# TC377TP_1.net
KiCad netlist of a schematic drawn in Altium Designer
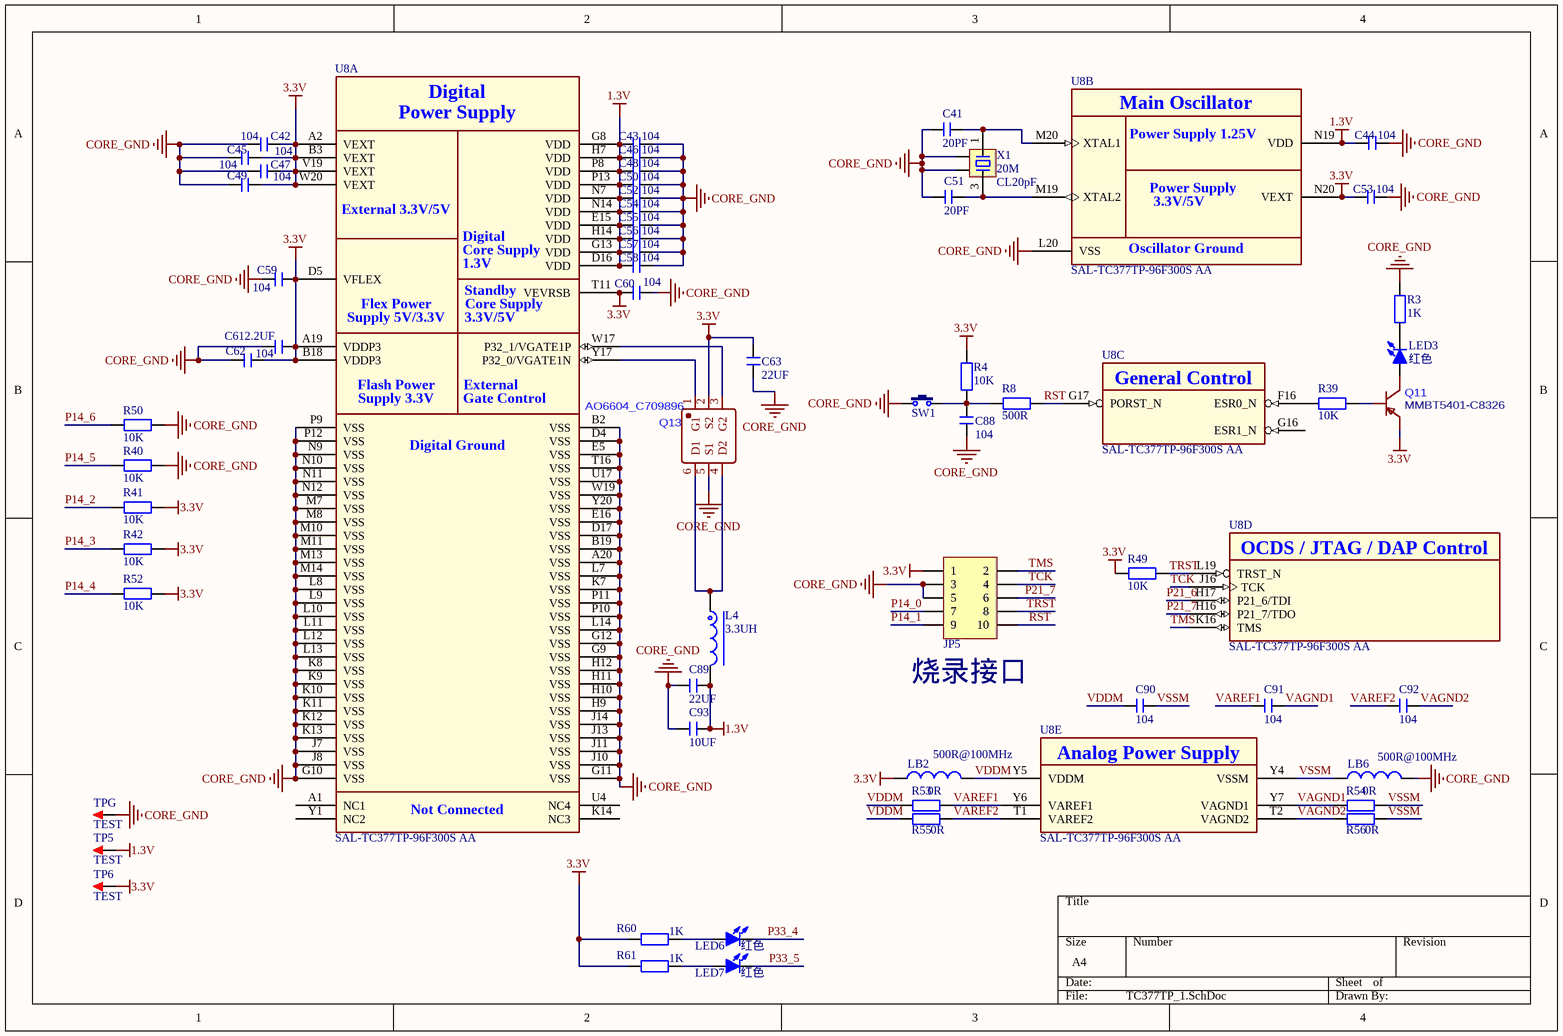
[diagram p0: TC377TP_1.SchDoc]

(export (version "E")
  (design (tool "Eeschema 10.0.6"))
  (components
    (comp (ref "C41")
      (value "20PF")
      (footprint "C 0603_L")
      (description "无极性贴片电容")
      (fields (field (name "版权归属") "源创客"))
      (libsource (lib "3.1   - 电阻-电容-电感") (part "C"))
    )
    (comp (ref "C42")
      (value "104")
      (footprint "C 0603_L")
      (description "无极性贴片电容")
      (fields (field (name "版权归属") "源创客"))
      (libsource (lib "3.1   - 电阻-电容-电感") (part "C"))
    )
    (comp (ref "C43")
      (value "104")
      (footprint "C 0603_L")
      (description "无极性贴片电容")
      (fields (field (name "版权归属") "源创客"))
      (libsource (lib "3.1   - 电阻-电容-电感") (part "C"))
    )
    (comp (ref "C44")
      (value "104")
      (footprint "C 0603_L")
      (description "无极性贴片电容")
      (fields (field (name "版权归属") "源创客"))
      (libsource (lib "3.1   - 电阻-电容-电感") (part "C"))
    )
    (comp (ref "C45")
      (value "104")
      (footprint "C 0603_L")
      (description "无极性贴片电容")
      (fields (field (name "版权归属") "源创客"))
      (libsource (lib "3.1   - 电阻-电容-电感") (part "C"))
    )
    (comp (ref "C46")
      (value "104")
      (footprint "C 0603_L")
      (description "无极性贴片电容")
      (fields (field (name "版权归属") "源创客"))
      (libsource (lib "3.1   - 电阻-电容-电感") (part "C"))
    )
    (comp (ref "C47")
      (value "104")
      (footprint "C 0603_L")
      (description "无极性贴片电容")
      (fields (field (name "版权归属") "源创客"))
      (libsource (lib "3.1   - 电阻-电容-电感") (part "C"))
    )
    (comp (ref "C48")
      (value "104")
      (footprint "C 0603_L")
      (description "无极性贴片电容")
      (fields (field (name "版权归属") "源创客"))
      (libsource (lib "3.1   - 电阻-电容-电感") (part "C"))
    )
    (comp (ref "C49")
      (value "104")
      (footprint "C 0603_L")
      (description "无极性贴片电容")
      (fields (field (name "版权归属") "源创客"))
      (libsource (lib "3.1   - 电阻-电容-电感") (part "C"))
    )
    (comp (ref "C50")
      (value "104")
      (footprint "C 0603_L")
      (description "无极性贴片电容")
      (fields (field (name "版权归属") "源创客"))
      (libsource (lib "3.1   - 电阻-电容-电感") (part "C"))
    )
    (comp (ref "C51")
      (value "20PF")
      (footprint "C 0603_L")
      (description "无极性贴片电容")
      (fields (field (name "版权归属") "源创客"))
      (libsource (lib "3.1   - 电阻-电容-电感") (part "C"))
    )
    (comp (ref "C52")
      (value "104")
      (footprint "C 0603_L")
      (description "无极性贴片电容")
      (fields (field (name "版权归属") "源创客"))
      (libsource (lib "3.1   - 电阻-电容-电感") (part "C"))
    )
    (comp (ref "C53")
      (value "104")
      (footprint "C 0603_L")
      (description "无极性贴片电容")
      (fields (field (name "版权归属") "源创客"))
      (libsource (lib "3.1   - 电阻-电容-电感") (part "C"))
    )
    (comp (ref "C54")
      (value "104")
      (footprint "C 0603_L")
      (description "无极性贴片电容")
      (fields (field (name "版权归属") "源创客"))
      (libsource (lib "3.1   - 电阻-电容-电感") (part "C"))
    )
    (comp (ref "C55")
      (value "104")
      (footprint "C 0603_L")
      (description "无极性贴片电容")
      (fields (field (name "版权归属") "源创客"))
      (libsource (lib "3.1   - 电阻-电容-电感") (part "C"))
    )
    (comp (ref "C56")
      (value "104")
      (footprint "C 0603_L")
      (description "无极性贴片电容")
      (fields (field (name "版权归属") "源创客"))
      (libsource (lib "3.1   - 电阻-电容-电感") (part "C"))
    )
    (comp (ref "C57")
      (value "104")
      (footprint "C 0603_L")
      (description "无极性贴片电容")
      (fields (field (name "版权归属") "源创客"))
      (libsource (lib "3.1   - 电阻-电容-电感") (part "C"))
    )
    (comp (ref "C58")
      (value "104")
      (footprint "C 0603_L")
      (description "无极性贴片电容")
      (fields (field (name "版权归属") "源创客"))
      (libsource (lib "3.1   - 电阻-电容-电感") (part "C"))
    )
    (comp (ref "C59")
      (value "104")
      (footprint "C 0603_L")
      (description "无极性贴片电容")
      (fields (field (name "版权归属") "源创客"))
      (libsource (lib "3.1   - 电阻-电容-电感") (part "C"))
    )
    (comp (ref "C60")
      (value "104")
      (footprint "C 0603_L")
      (description "无极性贴片电容")
      (fields (field (name "版权归属") "源创客"))
      (libsource (lib "3.1   - 电阻-电容-电感") (part "C"))
    )
    (comp (ref "C61")
      (value "2.2UF")
      (footprint "C 0603_L")
      (description "无极性贴片电容")
      (fields (field (name "版权归属") "源创客"))
      (libsource (lib "3.1   - 电阻-电容-电感") (part "C"))
    )
    (comp (ref "C62")
      (value "104")
      (footprint "C 0603_L")
      (description "无极性贴片电容")
      (fields (field (name "版权归属") "源创客"))
      (libsource (lib "3.1   - 电阻-电容-电感") (part "C"))
    )
    (comp (ref "C63")
      (value "22UF")
      (footprint "C 0805_L")
      (description "无极性贴片电容")
      (fields (field (name "版权归属") "源创客"))
      (libsource (lib "3.1   - 电阻-电容-电感") (part "C"))
    )
    (comp (ref "C88")
      (value "104")
      (footprint "C 0603_L")
      (description "无极性贴片电容")
      (fields (field (name "版权归属") "源创客"))
      (libsource (lib "3.1   - 电阻-电容-电感") (part "C"))
    )
    (comp (ref "C89")
      (value "22UF")
      (footprint "C 0805_L")
      (description "无极性贴片电容")
      (fields (field (name "版权归属") "源创客"))
      (libsource (lib "3.1   - 电阻-电容-电感") (part "C"))
    )
    (comp (ref "C90")
      (value "104")
      (footprint "C 0603_L")
      (description "无极性贴片电容")
      (fields (field (name "版权归属") "源创客"))
      (libsource (lib "3.1   - 电阻-电容-电感") (part "C"))
    )
    (comp (ref "C91")
      (value "104")
      (footprint "C 0603_L")
      (description "无极性贴片电容")
      (fields (field (name "版权归属") "源创客"))
      (libsource (lib "3.1   - 电阻-电容-电感") (part "C"))
    )
    (comp (ref "C92")
      (value "104")
      (footprint "C 0603_L")
      (description "无极性贴片电容")
      (fields (field (name "版权归属") "源创客"))
      (libsource (lib "3.1   - 电阻-电容-电感") (part "C"))
    )
    (comp (ref "C93")
      (value "10UF")
      (footprint "C 0805_L")
      (description "无极性贴片电容")
      (fields (field (name "版权归属") "源创客"))
      (libsource (lib "3.1   - 电阻-电容-电感") (part "C"))
    )
    (comp (ref "JP5")
      (value "Header 5X2")
      (footprint "IDC2.54-LI-2x5P")
      (description "5*2P接插件")
      (fields (field (name "版权归属") "源创客"))
      (libsource (lib "4.6   - 接插件-脚距2.54") (part "Header 5X2"))
    )
    (comp (ref "L4")
      (value "3.3UH")
      (footprint "L-SMD-0420")
      (description "贴片功率电感")
      (fields (field (name "版权归属") "源创客"))
      (libsource (lib "3.1   - 电阻-电容-电感") (part "L-CD"))
    )
    (comp (ref "LB2")
      (value "500R@100MHz")
      (footprint "FB 0603_L")
      (description "磁珠")
      (fields (field (name "版权归属") "源创客"))
      (libsource (lib "3.1   - 电阻-电容-电感") (part "LB"))
    )
    (comp (ref "LB6")
      (value "500R@100MHz")
      (footprint "FB 0603_L")
      (description "磁珠")
      (fields (field (name "版权归属") "源创客"))
      (libsource (lib "3.1   - 电阻-电容-电感") (part "LB"))
    )
    (comp (ref "LED3")
      (value "红色")
      (footprint "LED 0603Y")
      (description "贴片LED")
      (fields (field (name "版权归属") "源创客"))
      (libsource (lib "9.1   - LED") (part "LED-SMD"))
    )
    (comp (ref "LED6")
      (value "红色")
      (footprint "LED 0603Y")
      (description "贴片LED")
      (fields (field (name "版权归属") "源创客"))
      (libsource (lib "9.1   - LED") (part "LED-SMD"))
    )
    (comp (ref "LED7")
      (value "红色")
      (footprint "LED 0603Y")
      (description "贴片LED")
      (fields (field (name "版权归属") "源创客"))
      (libsource (lib "9.1   - LED") (part "LED-SMD"))
    )
    (comp (ref "Q11")
      (value "MMBT5401-C8326")
      (footprint "SOT23-3L")
      (libsource (lib "MMBT5401") (part "MMBT5401-C8326"))
    )
    (comp (ref "Q13")
      (value "AO6604_C709896")
      (footprint "TSOP-6_L3.0-W1.5-P0.95-LS2.8-BR")
      (libsource (lib "AO6604_C709896") (part "AO6604_C709896"))
    )
    (comp (ref "R3")
      (value "1K")
      (footprint "R 0603_L")
      (description "贴片电阻")
      (fields (field (name "版权归属") "源创客"))
      (libsource (lib "3.1   - 电阻-电容-电感") (part "R"))
    )
    (comp (ref "R4")
      (value "10K")
      (footprint "R 0603_L")
      (description "贴片电阻")
      (fields (field (name "版权归属") "源创客"))
      (libsource (lib "3.1   - 电阻-电容-电感") (part "R"))
    )
    (comp (ref "R8")
      (value "500R")
      (footprint "R 0603_L")
      (description "贴片电阻")
      (fields (field (name "版权归属") "源创客"))
      (libsource (lib "3.1   - 电阻-电容-电感") (part "R"))
    )
    (comp (ref "R39")
      (value "10K")
      (footprint "R 0603_L")
      (description "贴片电阻")
      (fields (field (name "版权归属") "源创客"))
      (libsource (lib "3.1   - 电阻-电容-电感") (part "R"))
    )
    (comp (ref "R40")
      (value "10K")
      (footprint "R 0603_L")
      (description "贴片电阻")
      (fields (field (name "版权归属") "源创客"))
      (libsource (lib "3.1   - 电阻-电容-电感") (part "R"))
    )
    (comp (ref "R41")
      (value "10K")
      (footprint "R 0603_L")
      (description "贴片电阻")
      (fields (field (name "版权归属") "源创客"))
      (libsource (lib "3.1   - 电阻-电容-电感") (part "R"))
    )
    (comp (ref "R42")
      (value "10K")
      (footprint "R 0603_L")
      (description "贴片电阻")
      (fields (field (name "版权归属") "源创客"))
      (libsource (lib "3.1   - 电阻-电容-电感") (part "R"))
    )
    (comp (ref "R49")
      (value "10K")
      (footprint "R 0805_L")
      (description "贴片电阻")
      (fields (field (name "版权归属") "源创客"))
      (libsource (lib "3.1   - 电阻-电容-电感") (part "R"))
    )
    (comp (ref "R50")
      (value "10K")
      (footprint "R 0603_L")
      (description "贴片电阻")
      (fields (field (name "版权归属") "源创客"))
      (libsource (lib "3.1   - 电阻-电容-电感") (part "R"))
    )
    (comp (ref "R52")
      (value "10K")
      (footprint "R 0603_L")
      (description "贴片电阻")
      (fields (field (name "版权归属") "源创客"))
      (libsource (lib "3.1   - 电阻-电容-电感") (part "R"))
    )
    (comp (ref "R53")
      (value "0R")
      (footprint "R 0603_L")
      (description "贴片电阻")
      (fields (field (name "版权归属") "源创客"))
      (libsource (lib "3.1   - 电阻-电容-电感") (part "R"))
    )
    (comp (ref "R54")
      (value "0R")
      (footprint "R 0603_L")
      (description "贴片电阻")
      (fields (field (name "版权归属") "源创客"))
      (libsource (lib "3.1   - 电阻-电容-电感") (part "R"))
    )
    (comp (ref "R55")
      (value "0R")
      (footprint "R 0603_L")
      (description "贴片电阻")
      (fields (field (name "版权归属") "源创客"))
      (libsource (lib "3.1   - 电阻-电容-电感") (part "R"))
    )
    (comp (ref "R56")
      (value "0R")
      (footprint "R 0603_L")
      (description "贴片电阻")
      (fields (field (name "版权归属") "源创客"))
      (libsource (lib "3.1   - 电阻-电容-电感") (part "R"))
    )
    (comp (ref "R60")
      (value "1K")
      (footprint "R 0603_L")
      (description "贴片电阻")
      (fields (field (name "版权归属") "源创客"))
      (libsource (lib "3.1   - 电阻-电容-电感") (part "R"))
    )
    (comp (ref "R61")
      (value "1K")
      (footprint "R 0603_L")
      (description "贴片电阻")
      (fields (field (name "版权归属") "源创客"))
      (libsource (lib "3.1   - 电阻-电容-电感") (part "R"))
    )
    (comp (ref "SW1")
      (value "3x6x5")
      (footprint "TSW SMD-3*6*2.5")
      (description "3x6轻触开关")
      (fields (field (name "版权归属") "源创客"))
      (libsource (lib "5.1   - 按键-开关") (part "TSW 3x6"))
    )
    (comp (ref "TP5")
      (value "TEST")
      (footprint "TEST 1.6")
      (description "测试点")
      (fields (field (name "版权归属") "源创客"))
      (libsource (lib "15.1 - 未分类器件") (part "TEST"))
    )
    (comp (ref "TP6")
      (value "TEST")
      (footprint "TEST 1.6")
      (description "测试点")
      (fields (field (name "版权归属") "源创客"))
      (libsource (lib "15.1 - 未分类器件") (part "TEST"))
    )
    (comp (ref "TPG")
      (value "TEST")
      (footprint "TEST 1.6")
      (description "测试点")
      (fields (field (name "版权归属") "源创客"))
      (libsource (lib "15.1 - 未分类器件") (part "TEST"))
    )
    (comp (ref "U8")
      (value "SAL-TC377TP-96F300S AA")
      (footprint "BGA292C80P20X20")
      (description "32-Bit Single-Chip Microcontroller")
      (fields (field (name "MANUFACTURER") "Infineon Technologies"))
      (libsource (lib "SAL-TC377TP-96F300S AA") (part "SAL-TC377TP-96F300S AA"))
    )
    (comp (ref "X1")
      (value "20M")
      (footprint "OSC 3225-4P")
      (description "4脚无源晶振")
      (fields (field (name "负载电容") "CL20pF") (field (name "版权归属") "源创客"))
      (libsource (lib "10.1 - 保险丝-晶振") (part "XTAL-4P"))
    )
  )
  (nets
    (net (code "1") (name "/P14_0") (class "Default")
      (node (ref "JP5") (pin "7") (pinfunction "7_7") (pintype "passive"))
    )
    (net (code "2") (name "/P14_1") (class "Default")
      (node (ref "JP5") (pin "9") (pinfunction "9_9") (pintype "passive"))
    )
    (net (code "3") (name "/P14_2") (class "Default")
      (node (ref "R41") (pin "1") (pinfunction "1_1") (pintype "passive"))
    )
    (net (code "4") (name "/P14_3") (class "Default")
      (node (ref "R42") (pin "1") (pinfunction "1_1") (pintype "passive"))
    )
    (net (code "5") (name "/P14_4") (class "Default")
      (node (ref "R52") (pin "1") (pinfunction "1_1") (pintype "passive"))
    )
    (net (code "6") (name "/P14_5") (class "Default")
      (node (ref "R40") (pin "1") (pinfunction "1_1") (pintype "passive"))
    )
    (net (code "7") (name "/P14_6") (class "Default")
      (node (ref "R50") (pin "1") (pinfunction "1_1") (pintype "passive"))
    )
    (net (code "8") (name "/P21_6") (class "Default")
      (node (ref "U8") (pin "H17") (pinfunction "P21_6/TDI_H17") (pintype "bidirectional"))
    )
    (net (code "9") (name "/P21_7") (class "Default")
      (node (ref "JP5") (pin "6") (pinfunction "6_6") (pintype "passive"))
      (node (ref "U8") (pin "H16") (pinfunction "P21_7/TDO_H16") (pintype "bidirectional"))
    )
    (net (code "10") (name "/P33_4") (class "Default")
      (node (ref "LED6") (pin "2") (pinfunction "K_2") (pintype "passive"))
    )
    (net (code "11") (name "/P33_5") (class "Default")
      (node (ref "LED7") (pin "2") (pinfunction "K_2") (pintype "passive"))
    )
    (net (code "12") (name "/RST") (class "Default")
      (node (ref "JP5") (pin "10") (pinfunction "10_10") (pintype "passive"))
      (node (ref "R8") (pin "2") (pinfunction "2_2") (pintype "passive"))
      (node (ref "U8") (pin "G17") (pinfunction "PORST_N_G17") (pintype "input"))
    )
    (net (code "13") (name "/TCK") (class "Default")
      (node (ref "JP5") (pin "4") (pinfunction "4_4") (pintype "passive"))
      (node (ref "U8") (pin "J16") (pinfunction "TCK_J16") (pintype "input"))
    )
    (net (code "14") (name "/TMS") (class "Default")
      (node (ref "JP5") (pin "2") (pinfunction "2_2") (pintype "passive"))
      (node (ref "U8") (pin "K16") (pinfunction "TMS_K16") (pintype "bidirectional"))
    )
    (net (code "15") (name "/TRST") (class "Default")
      (node (ref "JP5") (pin "8") (pinfunction "8_8") (pintype "passive"))
      (node (ref "R49") (pin "1") (pinfunction "1_1") (pintype "passive"))
      (node (ref "U8") (pin "L19") (pinfunction "TRST_N_L19") (pintype "input"))
    )
    (net (code "16") (name "/VAGND1") (class "Default")
      (node (ref "C91") (pin "1") (pinfunction "1_1") (pintype "passive"))
      (node (ref "R54") (pin "1") (pinfunction "1_1") (pintype "passive"))
      (node (ref "U8") (pin "Y7") (pinfunction "VAGND1_Y7") (pintype "power_in"))
    )
    (net (code "17") (name "/VAGND2") (class "Default")
      (node (ref "C92") (pin "1") (pinfunction "1_1") (pintype "passive"))
      (node (ref "R56") (pin "1") (pinfunction "1_1") (pintype "passive"))
      (node (ref "U8") (pin "T2") (pinfunction "VAGND2_T2") (pintype "power_in"))
    )
    (net (code "18") (name "/VAREF1") (class "Default")
      (node (ref "C91") (pin "2") (pinfunction "2_2") (pintype "passive"))
      (node (ref "R53") (pin "2") (pinfunction "2_2") (pintype "passive"))
      (node (ref "U8") (pin "Y6") (pinfunction "VAREF1_Y6") (pintype "power_in"))
    )
    (net (code "19") (name "/VAREF2") (class "Default")
      (node (ref "C92") (pin "2") (pinfunction "2_2") (pintype "passive"))
      (node (ref "R55") (pin "2") (pinfunction "2_2") (pintype "passive"))
      (node (ref "U8") (pin "T1") (pinfunction "VAREF2_T1") (pintype "power_in"))
    )
    (net (code "20") (name "/VDDM") (class "Default")
      (node (ref "C90") (pin "2") (pinfunction "2_2") (pintype "passive"))
      (node (ref "LB2") (pin "2") (pinfunction "2_2") (pintype "passive"))
      (node (ref "R53") (pin "1") (pinfunction "1_1") (pintype "passive"))
      (node (ref "R55") (pin "1") (pinfunction "1_1") (pintype "passive"))
      (node (ref "U8") (pin "Y5") (pinfunction "VDDM_Y5") (pintype "power_in"))
    )
    (net (code "21") (name "/VSSM") (class "Default")
      (node (ref "C90") (pin "1") (pinfunction "1_1") (pintype "passive"))
      (node (ref "LB6") (pin "1") (pinfunction "1_1") (pintype "passive"))
      (node (ref "R54") (pin "2") (pinfunction "2_2") (pintype "passive"))
      (node (ref "R56") (pin "2") (pinfunction "2_2") (pintype "passive"))
      (node (ref "U8") (pin "Y4") (pinfunction "VSSM_Y4") (pintype "power_in"))
    )
    (net (code "22") (name "1.3V") (class "Default")
      (node (ref "C43") (pin "2") (pinfunction "2_2") (pintype "passive"))
      (node (ref "C44") (pin "2") (pinfunction "2_2") (pintype "passive"))
      (node (ref "C46") (pin "2") (pinfunction "2_2") (pintype "passive"))
      (node (ref "C48") (pin "2") (pinfunction "2_2") (pintype "passive"))
      (node (ref "C50") (pin "2") (pinfunction "2_2") (pintype "passive"))
      (node (ref "C52") (pin "2") (pinfunction "2_2") (pintype "passive"))
      (node (ref "C54") (pin "2") (pinfunction "2_2") (pintype "passive"))
      (node (ref "C55") (pin "2") (pinfunction "2_2") (pintype "passive"))
      (node (ref "C56") (pin "2") (pinfunction "2_2") (pintype "passive"))
      (node (ref "C57") (pin "2") (pinfunction "2_2") (pintype "passive"))
      (node (ref "C58") (pin "2") (pinfunction "2_2") (pintype "passive"))
      (node (ref "C89") (pin "1") (pinfunction "1_1") (pintype "passive"))
      (node (ref "C93") (pin "1") (pinfunction "1_1") (pintype "passive"))
      (node (ref "L4") (pin "2") (pinfunction "2_2") (pintype "passive"))
      (node (ref "TP5") (pin "1") (pinfunction "1_1") (pintype "passive"))
      (node (ref "U8") (pin "D16") (pinfunction "VDD_D16") (pintype "power_in"))
      (node (ref "U8") (pin "E15") (pinfunction "VDD_E15") (pintype "power_in"))
      (node (ref "U8") (pin "G13") (pinfunction "VDD_G13") (pintype "power_in"))
      (node (ref "U8") (pin "G8") (pinfunction "VDD_G8") (pintype "power_in"))
      (node (ref "U8") (pin "H14") (pinfunction "VDD_H14") (pintype "power_in"))
      (node (ref "U8") (pin "H7") (pinfunction "VDD_H7") (pintype "power_in"))
      (node (ref "U8") (pin "N14") (pinfunction "VDD_N14") (pintype "power_in"))
      (node (ref "U8") (pin "N19") (pinfunction "VDD_N19") (pintype "power_in"))
      (node (ref "U8") (pin "N7") (pinfunction "VDD_N7") (pintype "power_in"))
      (node (ref "U8") (pin "P13") (pinfunction "VDD_P13") (pintype "power_in"))
      (node (ref "U8") (pin "P8") (pinfunction "VDD_P8") (pintype "power_in"))
    )
    (net (code "23") (name "3.3V") (class "Default")
      (node (ref "C42") (pin "1") (pinfunction "1_1") (pintype "passive"))
      (node (ref "C45") (pin "1") (pinfunction "1_1") (pintype "passive"))
      (node (ref "C47") (pin "1") (pinfunction "1_1") (pintype "passive"))
      (node (ref "C49") (pin "1") (pinfunction "1_1") (pintype "passive"))
      (node (ref "C53") (pin "2") (pinfunction "2_2") (pintype "passive"))
      (node (ref "C59") (pin "1") (pinfunction "1_1") (pintype "passive"))
      (node (ref "C60") (pin "2") (pinfunction "2_2") (pintype "passive"))
      (node (ref "C61") (pin "1") (pinfunction "1_1") (pintype "passive"))
      (node (ref "C62") (pin "1") (pinfunction "1_1") (pintype "passive"))
      (node (ref "C63") (pin "2") (pinfunction "2_2") (pintype "passive"))
      (node (ref "JP5") (pin "1") (pinfunction "1_1") (pintype "passive"))
      (node (ref "LB2") (pin "1") (pinfunction "1_1") (pintype "passive"))
      (node (ref "Q11") (pin "2") (pinfunction "E_2") (pintype "passive"))
      (node (ref "Q13") (pin "2") (pinfunction "S2_2") (pintype "passive"))
      (node (ref "R4") (pin "2") (pinfunction "2_2") (pintype "passive"))
      (node (ref "R41") (pin "2") (pinfunction "2_2") (pintype "passive"))
      (node (ref "R42") (pin "2") (pinfunction "2_2") (pintype "passive"))
      (node (ref "R49") (pin "2") (pinfunction "2_2") (pintype "passive"))
      (node (ref "R52") (pin "2") (pinfunction "2_2") (pintype "passive"))
      (node (ref "R60") (pin "2") (pinfunction "2_2") (pintype "passive"))
      (node (ref "R61") (pin "2") (pinfunction "2_2") (pintype "passive"))
      (node (ref "TP6") (pin "1") (pinfunction "1_1") (pintype "passive"))
      (node (ref "U8") (pin "A19") (pinfunction "VDDP3_A19") (pintype "power_in"))
      (node (ref "U8") (pin "A2") (pinfunction "VEXT_A2") (pintype "power_in"))
      (node (ref "U8") (pin "B18") (pinfunction "VDDP3_B18") (pintype "power_in"))
      (node (ref "U8") (pin "B3") (pinfunction "VEXT_B3") (pintype "power_in"))
      (node (ref "U8") (pin "D5") (pinfunction "VFLEX_D5") (pintype "power_in"))
      (node (ref "U8") (pin "N20") (pinfunction "VEXT_N20") (pintype "power_in"))
      (node (ref "U8") (pin "T11") (pinfunction "VEVRSB_T11") (pintype "power_in"))
      (node (ref "U8") (pin "V19") (pinfunction "VEXT_V19") (pintype "power_in"))
      (node (ref "U8") (pin "W20") (pinfunction "VEXT_W20") (pintype "power_in"))
    )
    (net (code "24") (name "CORE_GND") (class "Default")
      (node (ref "C41") (pin "2") (pinfunction "2_2") (pintype "passive"))
      (node (ref "C42") (pin "2") (pinfunction "2_2") (pintype "passive"))
      (node (ref "C43") (pin "1") (pinfunction "1_1") (pintype "passive"))
      (node (ref "C44") (pin "1") (pinfunction "1_1") (pintype "passive"))
      (node (ref "C45") (pin "2") (pinfunction "2_2") (pintype "passive"))
      (node (ref "C46") (pin "1") (pinfunction "1_1") (pintype "passive"))
      (node (ref "C47") (pin "2") (pinfunction "2_2") (pintype "passive"))
      (node (ref "C48") (pin "1") (pinfunction "1_1") (pintype "passive"))
      (node (ref "C49") (pin "2") (pinfunction "2_2") (pintype "passive"))
      (node (ref "C50") (pin "1") (pinfunction "1_1") (pintype "passive"))
      (node (ref "C51") (pin "2") (pinfunction "2_2") (pintype "passive"))
      (node (ref "C52") (pin "1") (pinfunction "1_1") (pintype "passive"))
      (node (ref "C53") (pin "1") (pinfunction "1_1") (pintype "passive"))
      (node (ref "C54") (pin "1") (pinfunction "1_1") (pintype "passive"))
      (node (ref "C55") (pin "1") (pinfunction "1_1") (pintype "passive"))
      (node (ref "C56") (pin "1") (pinfunction "1_1") (pintype "passive"))
      (node (ref "C57") (pin "1") (pinfunction "1_1") (pintype "passive"))
      (node (ref "C58") (pin "1") (pinfunction "1_1") (pintype "passive"))
      (node (ref "C59") (pin "2") (pinfunction "2_2") (pintype "passive"))
      (node (ref "C60") (pin "1") (pinfunction "1_1") (pintype "passive"))
      (node (ref "C61") (pin "2") (pinfunction "2_2") (pintype "passive"))
      (node (ref "C62") (pin "2") (pinfunction "2_2") (pintype "passive"))
      (node (ref "C63") (pin "1") (pinfunction "1_1") (pintype "passive"))
      (node (ref "C88") (pin "1") (pinfunction "1_1") (pintype "passive"))
      (node (ref "C89") (pin "2") (pinfunction "2_2") (pintype "passive"))
      (node (ref "C93") (pin "2") (pinfunction "2_2") (pintype "passive"))
      (node (ref "JP5") (pin "3") (pinfunction "3_3") (pintype "passive"))
      (node (ref "JP5") (pin "5") (pinfunction "5_5") (pintype "passive"))
      (node (ref "LB6") (pin "2") (pinfunction "2_2") (pintype "passive"))
      (node (ref "Q13") (pin "5") (pinfunction "S1_5") (pintype "passive"))
      (node (ref "R3") (pin "1") (pinfunction "1_1") (pintype "passive"))
      (node (ref "R40") (pin "2") (pinfunction "2_2") (pintype "passive"))
      (node (ref "R50") (pin "2") (pinfunction "2_2") (pintype "passive"))
      (node (ref "SW1") (pin "1") (pinfunction "1_1") (pintype "passive"))
      (node (ref "TPG") (pin "1") (pinfunction "1_1") (pintype "passive"))
      (node (ref "U8") (pin "A20") (pinfunction "VSS_A20") (pintype "power_in"))
      (node (ref "U8") (pin "B19") (pinfunction "VSS_B19") (pintype "power_in"))
      (node (ref "U8") (pin "B2") (pinfunction "VSS_B2") (pintype "power_in"))
      (node (ref "U8") (pin "D17") (pinfunction "VSS_D17") (pintype "power_in"))
      (node (ref "U8") (pin "D4") (pinfunction "VSS_D4") (pintype "power_in"))
      (node (ref "U8") (pin "E16") (pinfunction "VSS_E16") (pintype "power_in"))
      (node (ref "U8") (pin "E5") (pinfunction "VSS_E5") (pintype "power_in"))
      (node (ref "U8") (pin "G10") (pinfunction "VSS_G10") (pintype "power_in"))
      (node (ref "U8") (pin "G11") (pinfunction "VSS_G11") (pintype "power_in"))
      (node (ref "U8") (pin "G12") (pinfunction "VSS_G12") (pintype "power_in"))
      (node (ref "U8") (pin "G9") (pinfunction "VSS_G9") (pintype "power_in"))
      (node (ref "U8") (pin "H10") (pinfunction "VSS_H10") (pintype "power_in"))
      (node (ref "U8") (pin "H11") (pinfunction "VSS_H11") (pintype "power_in"))
      (node (ref "U8") (pin "H12") (pinfunction "VSS_H12") (pintype "power_in"))
      (node (ref "U8") (pin "H9") (pinfunction "VSS_H9") (pintype "power_in"))
      (node (ref "U8") (pin "J10") (pinfunction "VSS_J10") (pintype "power_in"))
      (node (ref "U8") (pin "J11") (pinfunction "VSS_J11") (pintype "power_in"))
      (node (ref "U8") (pin "J13") (pinfunction "VSS_J13") (pintype "power_in"))
      (node (ref "U8") (pin "J14") (pinfunction "VSS_J14") (pintype "power_in"))
      (node (ref "U8") (pin "J7") (pinfunction "VSS_J7") (pintype "power_in"))
      (node (ref "U8") (pin "J8") (pinfunction "VSS_J8") (pintype "power_in"))
      (node (ref "U8") (pin "K10") (pinfunction "VSS_K10") (pintype "power_in"))
      (node (ref "U8") (pin "K11") (pinfunction "VSS_K11") (pintype "power_in"))
      (node (ref "U8") (pin "K12") (pinfunction "VSS_K12") (pintype "power_in"))
      (node (ref "U8") (pin "K13") (pinfunction "VSS_K13") (pintype "power_in"))
      (node (ref "U8") (pin "K7") (pinfunction "VSS_K7") (pintype "power_in"))
      (node (ref "U8") (pin "K8") (pinfunction "VSS_K8") (pintype "power_in"))
      (node (ref "U8") (pin "K9") (pinfunction "VSS_K9") (pintype "power_in"))
      (node (ref "U8") (pin "L10") (pinfunction "VSS_L10") (pintype "power_in"))
      (node (ref "U8") (pin "L11") (pinfunction "VSS_L11") (pintype "power_in"))
      (node (ref "U8") (pin "L12") (pinfunction "VSS_L12") (pintype "power_in"))
      (node (ref "U8") (pin "L13") (pinfunction "VSS_L13") (pintype "power_in"))
      (node (ref "U8") (pin "L14") (pinfunction "VSS_L14") (pintype "power_in"))
      (node (ref "U8") (pin "L20") (pinfunction "VSS_L20") (pintype "power_in"))
      (node (ref "U8") (pin "L7") (pinfunction "VSS_L7") (pintype "power_in"))
      (node (ref "U8") (pin "L8") (pinfunction "VSS_L8") (pintype "power_in"))
      (node (ref "U8") (pin "L9") (pinfunction "VSS_L9") (pintype "power_in"))
      (node (ref "U8") (pin "M10") (pinfunction "VSS_M10") (pintype "power_in"))
      (node (ref "U8") (pin "M11") (pinfunction "VSS_M11") (pintype "power_in"))
      (node (ref "U8") (pin "M13") (pinfunction "VSS_M13") (pintype "power_in"))
      (node (ref "U8") (pin "M14") (pinfunction "VSS_M14") (pintype "power_in"))
      (node (ref "U8") (pin "M7") (pinfunction "VSS_M7") (pintype "power_in"))
      (node (ref "U8") (pin "M8") (pinfunction "VSS_M8") (pintype "power_in"))
      (node (ref "U8") (pin "N10") (pinfunction "VSS_N10") (pintype "power_in"))
      (node (ref "U8") (pin "N11") (pinfunction "VSS_N11") (pintype "power_in"))
      (node (ref "U8") (pin "N12") (pinfunction "VSS_N12") (pintype "power_in"))
      (node (ref "U8") (pin "N9") (pinfunction "VSS_N9") (pintype "power_in"))
      (node (ref "U8") (pin "P10") (pinfunction "VSS_P10") (pintype "power_in"))
      (node (ref "U8") (pin "P11") (pinfunction "VSS_P11") (pintype "power_in"))
      (node (ref "U8") (pin "P12") (pinfunction "VSS_P12") (pintype "power_in"))
      (node (ref "U8") (pin "P9") (pinfunction "VSS_P9") (pintype "power_in"))
      (node (ref "U8") (pin "T16") (pinfunction "VSS_T16") (pintype "power_in"))
      (node (ref "U8") (pin "U17") (pinfunction "VSS_U17") (pintype "power_in"))
      (node (ref "U8") (pin "W19") (pinfunction "VSS_W19") (pintype "power_in"))
      (node (ref "U8") (pin "Y20") (pinfunction "VSS_Y20") (pintype "power_in"))
      (node (ref "X1") (pin "2") (pinfunction "2_2") (pintype "passive"))
      (node (ref "X1") (pin "4") (pinfunction "4_4") (pintype "passive"))
    )
    (net (code "25") (name "Net-(C88-Pad2)") (class "Default")
      (node (ref "C88") (pin "2") (pinfunction "2_2") (pintype "passive"))
      (node (ref "R4") (pin "1") (pinfunction "1_1") (pintype "passive"))
      (node (ref "R8") (pin "1") (pinfunction "1_1") (pintype "passive"))
      (node (ref "SW1") (pin "2") (pinfunction "2_2") (pintype "passive"))
    )
    (net (code "26") (name "Net-(LED3-A)") (class "Default")
      (node (ref "LED3") (pin "1") (pinfunction "A_1") (pintype "passive"))
      (node (ref "Q11") (pin "3") (pinfunction "C_3") (pintype "passive"))
    )
    (net (code "27") (name "Net-(LED3-K)") (class "Default")
      (node (ref "LED3") (pin "2") (pinfunction "K_2") (pintype "passive"))
      (node (ref "R3") (pin "2") (pinfunction "2_2") (pintype "passive"))
    )
    (net (code "28") (name "Net-(LED6-A)") (class "Default")
      (node (ref "LED6") (pin "1") (pinfunction "A_1") (pintype "passive"))
      (node (ref "R60") (pin "1") (pinfunction "1_1") (pintype "passive"))
    )
    (net (code "29") (name "Net-(LED7-A)") (class "Default")
      (node (ref "LED7") (pin "1") (pinfunction "A_1") (pintype "passive"))
      (node (ref "R61") (pin "1") (pinfunction "1_1") (pintype "passive"))
    )
    (net (code "30") (name "Net-(Q11-B)") (class "Default")
      (node (ref "Q11") (pin "1") (pinfunction "B_1") (pintype "passive"))
      (node (ref "R39") (pin "1") (pinfunction "1_1") (pintype "passive"))
    )
    (net (code "31") (name "Net-(Q13-D1)") (class "Default")
      (node (ref "L4") (pin "1") (pinfunction "1_1") (pintype "passive"))
      (node (ref "Q13") (pin "4") (pinfunction "D2_4") (pintype "passive"))
      (node (ref "Q13") (pin "6") (pinfunction "D1_6") (pintype "passive"))
    )
    (net (code "32") (name "Net-(Q13-G1)") (class "Default")
      (node (ref "Q13") (pin "1") (pinfunction "G1_1") (pintype "passive"))
      (node (ref "U8") (pin "Y17") (pinfunction "P32_0/VGATE1N_Y17") (pintype "bidirectional"))
    )
    (net (code "33") (name "Net-(Q13-G2)") (class "Default")
      (node (ref "Q13") (pin "3") (pinfunction "G2_3") (pintype "passive"))
      (node (ref "U8") (pin "W17") (pinfunction "P32_1/VGATE1P_W17") (pintype "bidirectional"))
    )
    (net (code "34") (name "Net-(U8B-XTAL1)") (class "Default")
      (node (ref "C41") (pin "1") (pinfunction "1_1") (pintype "passive"))
      (node (ref "U8") (pin "M20") (pinfunction "XTAL1_M20") (pintype "input"))
      (node (ref "X1") (pin "1") (pinfunction "1_1") (pintype "passive"))
    )
    (net (code "35") (name "Net-(U8B-XTAL2)") (class "Default")
      (node (ref "C51") (pin "1") (pinfunction "1_1") (pintype "passive"))
      (node (ref "U8") (pin "M19") (pinfunction "XTAL2_M19") (pintype "output"))
      (node (ref "X1") (pin "3") (pinfunction "3_3") (pintype "passive"))
    )
    (net (code "36") (name "Net-(U8C-ESR0_N)") (class "Default")
      (node (ref "R39") (pin "2") (pinfunction "2_2") (pintype "passive"))
      (node (ref "U8") (pin "F16") (pinfunction "ESR0_N_F16") (pintype "input"))
    )
    (net (code "37") (name "unconnected-(U8A-NC1-PadA1)") (class "Default")
      (node (ref "U8") (pin "A1") (pinfunction "NC1_A1") (pintype "passive"))
    )
    (net (code "38") (name "unconnected-(U8A-NC2-PadY1)") (class "Default")
      (node (ref "U8") (pin "Y1") (pinfunction "NC2_Y1") (pintype "passive"))
    )
    (net (code "39") (name "unconnected-(U8A-NC3-PadK14)") (class "Default")
      (node (ref "U8") (pin "K14") (pinfunction "NC3_K14") (pintype "passive"))
    )
    (net (code "40") (name "unconnected-(U8A-NC4-PadU4)") (class "Default")
      (node (ref "U8") (pin "U4") (pinfunction "NC4_U4") (pintype "passive"))
    )
    (net (code "41") (name "unconnected-(U8C-ESR1_N-PadG16)") (class "Default")
      (node (ref "U8") (pin "G16") (pinfunction "ESR1_N_G16") (pintype "input"))
    )
  )
)
